# SparkFun_IMU_Breakout_ICM-20948.net
KiCad netlist of a schematic drawn in EAGLE
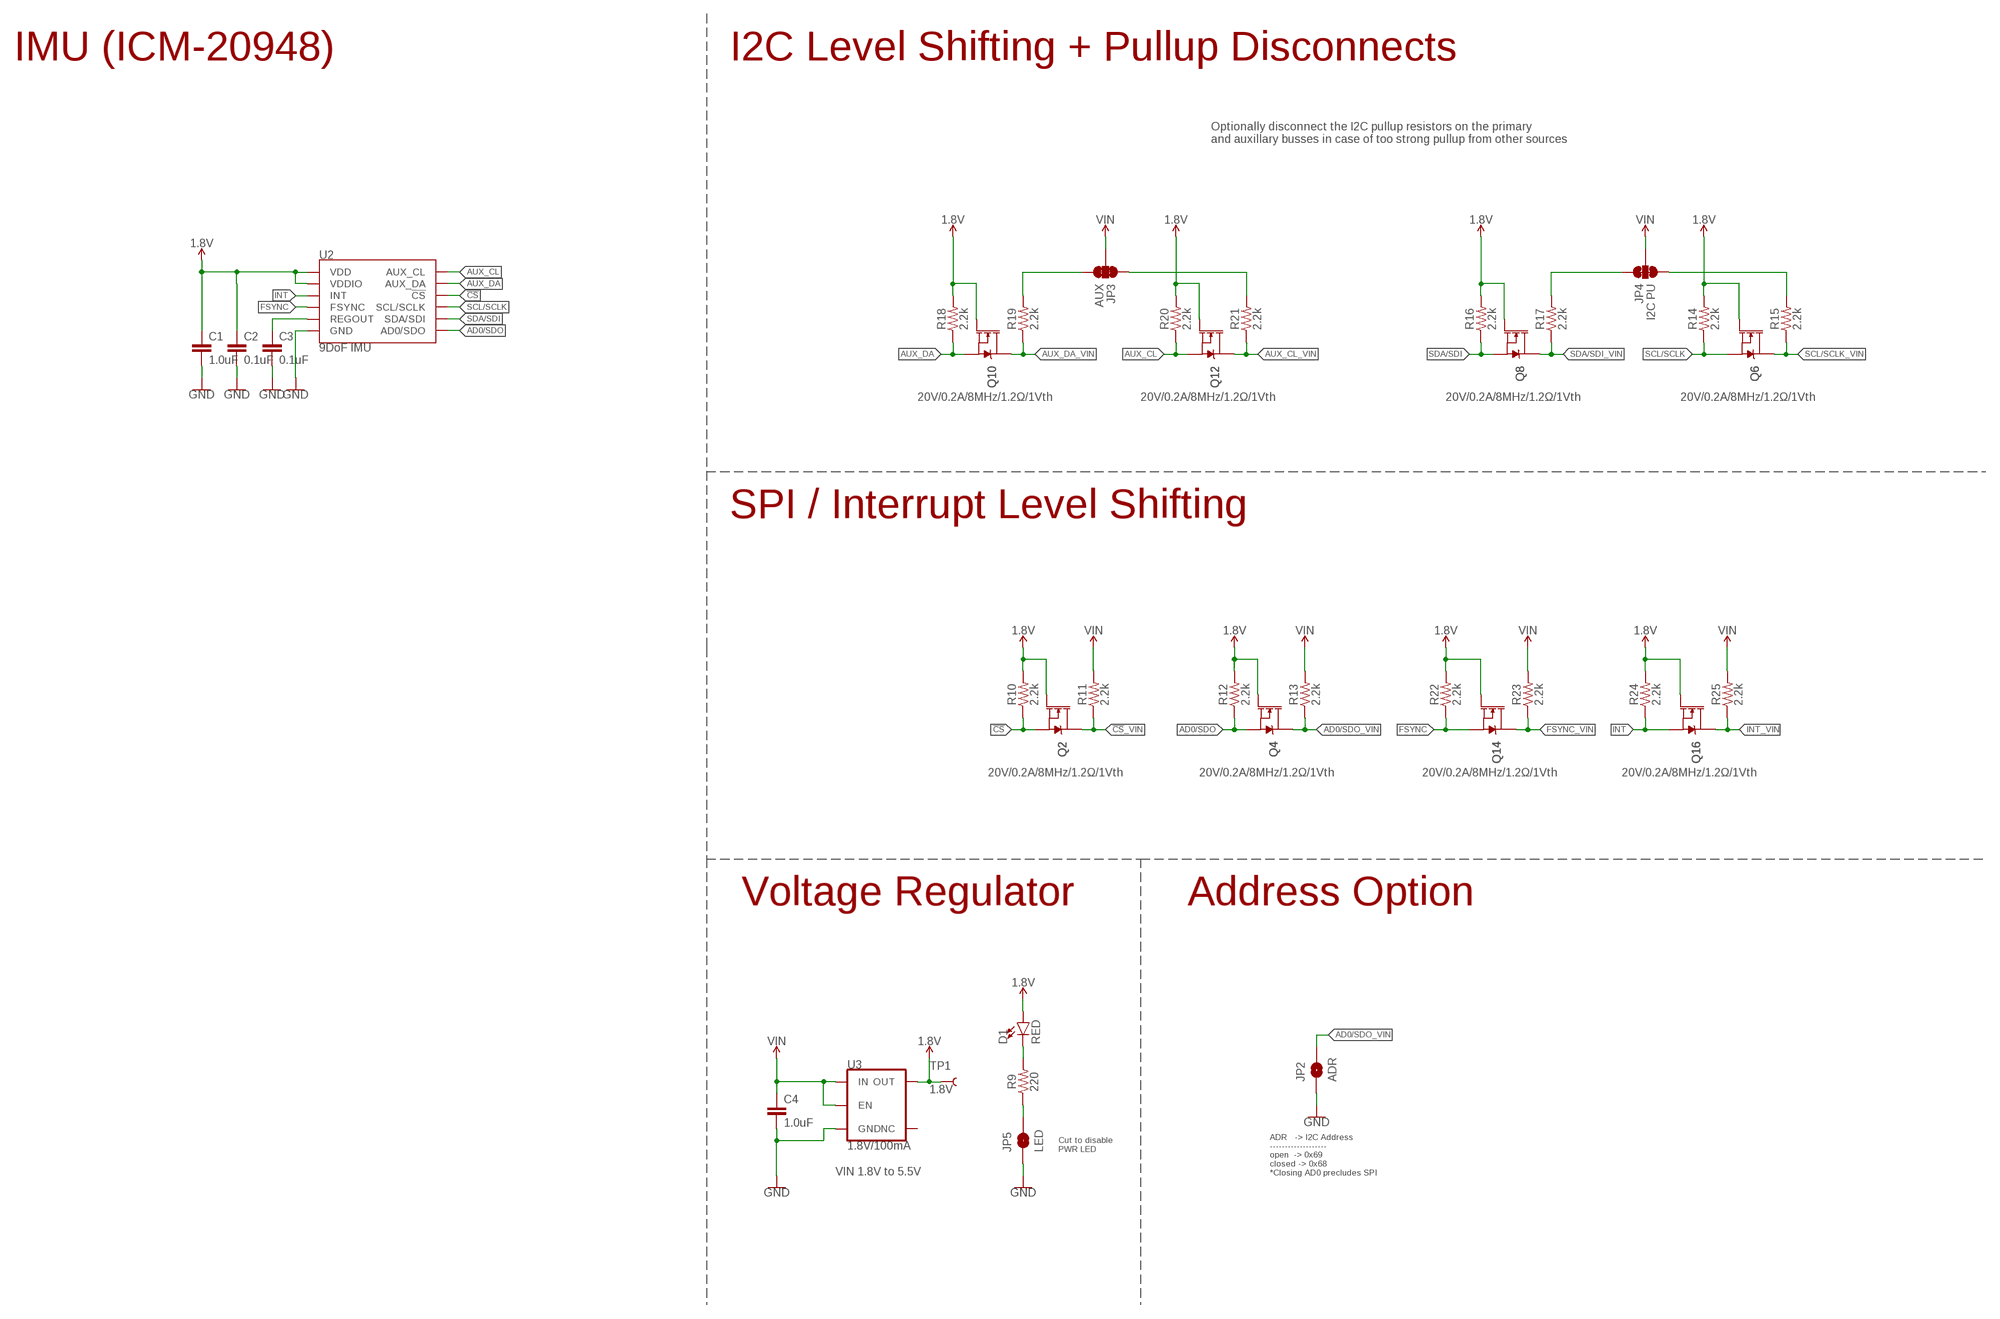
[diagram p0: schematic, sheet 1]

(export (version "E")
  (design (tool "Eeschema 10.0.6"))
  (components
    (comp (ref "C1")
      (value "1.0uF")
      (footprint "eagle-import:0603")
      (libsource (lib "eagle-import") (part "1.0UF-0603-16V-10%-X7R"))
    )
    (comp (ref "C2")
      (value "0.1uF")
      (footprint "eagle-import:0603")
      (libsource (lib "eagle-import") (part "0.1UF-0603-25V-5%"))
    )
    (comp (ref "C3")
      (value "0.1uF")
      (footprint "eagle-import:0603")
      (libsource (lib "eagle-import") (part "0.1UF-0603-25V-5%"))
    )
    (comp (ref "C4")
      (value "1.0uF")
      (footprint "eagle-import:0603")
      (libsource (lib "eagle-import") (part "1.0UF-0603-16V-10%-X7R"))
    )
    (comp (ref "D1")
      (value "RED")
      (footprint "eagle-import:LED-0603")
      (libsource (lib "eagle-import") (part "LED-RED0603"))
    )
    (comp (ref "JP2")
      (value "ADR")
      (footprint "eagle-import:SMT-JUMPER_2_NO_SILK")
      (libsource (lib "eagle-import") (part "JUMPER-SMT_2_NO_SILK"))
    )
    (comp (ref "JP3")
      (value "AUX")
      (footprint "eagle-import:SMT-JUMPER_3_2-NC_TRACE_SILK")
      (libsource (lib "eagle-import") (part "JUMPER-SMT_3_2-NC_TRACE_SILK"))
    )
    (comp (ref "JP4")
      (value "I2C PU")
      (footprint "eagle-import:SMT-JUMPER_3_2-NC_TRACE_SILK")
      (libsource (lib "eagle-import") (part "JUMPER-SMT_3_2-NC_TRACE_SILK"))
    )
    (comp (ref "JP5")
      (value "LED")
      (footprint "eagle-import:SMT-JUMPER_2_NC_TRACE_SILK")
      (libsource (lib "eagle-import") (part "JUMPER-SMT_2_NC_TRACE_SILK"))
    )
    (comp (ref "Q2")
      (value "20V/0.2A/8MHz/1.2Ω/1Vth")
      (footprint "eagle-import:SOT-416FL")
      (libsource (lib "eagle-import") (part "MOSFET-NCH-RE1C002UN"))
    )
    (comp (ref "Q4")
      (value "20V/0.2A/8MHz/1.2Ω/1Vth")
      (footprint "eagle-import:SOT-416FL")
      (libsource (lib "eagle-import") (part "MOSFET-NCH-RE1C002UN"))
    )
    (comp (ref "Q6")
      (value "20V/0.2A/8MHz/1.2Ω/1Vth")
      (footprint "eagle-import:SOT-416FL")
      (libsource (lib "eagle-import") (part "MOSFET-NCH-RE1C002UN"))
    )
    (comp (ref "Q8")
      (value "20V/0.2A/8MHz/1.2Ω/1Vth")
      (footprint "eagle-import:SOT-416FL")
      (libsource (lib "eagle-import") (part "MOSFET-NCH-RE1C002UN"))
    )
    (comp (ref "Q10")
      (value "20V/0.2A/8MHz/1.2Ω/1Vth")
      (footprint "eagle-import:SOT-416FL")
      (libsource (lib "eagle-import") (part "MOSFET-NCH-RE1C002UN"))
    )
    (comp (ref "Q12")
      (value "20V/0.2A/8MHz/1.2Ω/1Vth")
      (footprint "eagle-import:SOT-416FL")
      (libsource (lib "eagle-import") (part "MOSFET-NCH-RE1C002UN"))
    )
    (comp (ref "Q14")
      (value "20V/0.2A/8MHz/1.2Ω/1Vth")
      (footprint "eagle-import:SOT-416FL")
      (libsource (lib "eagle-import") (part "MOSFET-NCH-RE1C002UN"))
    )
    (comp (ref "Q16")
      (value "20V/0.2A/8MHz/1.2Ω/1Vth")
      (footprint "eagle-import:SOT-416FL")
      (libsource (lib "eagle-import") (part "MOSFET-NCH-RE1C002UN"))
    )
    (comp (ref "R9")
      (value "220")
      (footprint "eagle-import:0603")
      (libsource (lib "eagle-import") (part "220OHM-0603-1/10W-1%"))
    )
    (comp (ref "R10")
      (value "2.2k")
      (footprint "eagle-import:0402-TIGHT")
      (libsource (lib "eagle-import") (part "2.2KOHM-0402T-1/16W-1%"))
    )
    (comp (ref "R11")
      (value "2.2k")
      (footprint "eagle-import:0402-TIGHT")
      (libsource (lib "eagle-import") (part "2.2KOHM-0402T-1/16W-1%"))
    )
    (comp (ref "R12")
      (value "2.2k")
      (footprint "eagle-import:0402-TIGHT")
      (libsource (lib "eagle-import") (part "2.2KOHM-0402T-1/16W-1%"))
    )
    (comp (ref "R13")
      (value "2.2k")
      (footprint "eagle-import:0402-TIGHT")
      (libsource (lib "eagle-import") (part "2.2KOHM-0402T-1/16W-1%"))
    )
    (comp (ref "R14")
      (value "2.2k")
      (footprint "eagle-import:0402-TIGHT")
      (libsource (lib "eagle-import") (part "2.2KOHM-0402T-1/16W-1%"))
    )
    (comp (ref "R15")
      (value "2.2k")
      (footprint "eagle-import:0402-TIGHT")
      (libsource (lib "eagle-import") (part "2.2KOHM-0402T-1/16W-1%"))
    )
    (comp (ref "R16")
      (value "2.2k")
      (footprint "eagle-import:0402-TIGHT")
      (libsource (lib "eagle-import") (part "2.2KOHM-0402T-1/16W-1%"))
    )
    (comp (ref "R17")
      (value "2.2k")
      (footprint "eagle-import:0402-TIGHT")
      (libsource (lib "eagle-import") (part "2.2KOHM-0402T-1/16W-1%"))
    )
    (comp (ref "R18")
      (value "2.2k")
      (footprint "eagle-import:0402-TIGHT")
      (libsource (lib "eagle-import") (part "2.2KOHM-0402T-1/16W-1%"))
    )
    (comp (ref "R19")
      (value "2.2k")
      (footprint "eagle-import:0402-TIGHT")
      (libsource (lib "eagle-import") (part "2.2KOHM-0402T-1/16W-1%"))
    )
    (comp (ref "R20")
      (value "2.2k")
      (footprint "eagle-import:0402-TIGHT")
      (libsource (lib "eagle-import") (part "2.2KOHM-0402T-1/16W-1%"))
    )
    (comp (ref "R21")
      (value "2.2k")
      (footprint "eagle-import:0402-TIGHT")
      (libsource (lib "eagle-import") (part "2.2KOHM-0402T-1/16W-1%"))
    )
    (comp (ref "R22")
      (value "2.2k")
      (footprint "eagle-import:0402-TIGHT")
      (libsource (lib "eagle-import") (part "2.2KOHM-0402T-1/16W-1%"))
    )
    (comp (ref "R23")
      (value "2.2k")
      (footprint "eagle-import:0402-TIGHT")
      (libsource (lib "eagle-import") (part "2.2KOHM-0402T-1/16W-1%"))
    )
    (comp (ref "R24")
      (value "2.2k")
      (footprint "eagle-import:0402-TIGHT")
      (libsource (lib "eagle-import") (part "2.2KOHM-0402T-1/16W-1%"))
    )
    (comp (ref "R25")
      (value "2.2k")
      (footprint "eagle-import:0402-TIGHT")
      (libsource (lib "eagle-import") (part "2.2KOHM-0402T-1/16W-1%"))
    )
    (comp (ref "TP1")
      (value "1.8V")
      (footprint "eagle-import:PAD.03X.03")
      (libsource (lib "eagle-import") (part "TEST-POINT3"))
    )
    (comp (ref "U2")
      (value "9DoF IMU")
      (footprint "eagle-import:QFN24-3X3")
      (libsource (lib "eagle-import") (part "ICM-20948"))
    )
    (comp (ref "U3")
      (value "1.8V/100mA")
      (footprint "eagle-import:SC70")
      (libsource (lib "eagle-import") (part "V_REG_SP6214-1.8V"))
    )
  )
  (nets
    (net (code "1") (name "/~{CS}") (class "Default")
      (node (ref "Q2") (pin "2") (pinfunction "S_2") (pintype "bidirectional"))
      (node (ref "R10") (pin "1") (pinfunction "1_1") (pintype "passive"))
      (node (ref "U2") (pin "22") (pinfunction "~{CS}_22") (pintype "bidirectional"))
    )
    (net (code "2") (name "/~{CS}_VIN") (class "Default")
      (node (ref "Q2") (pin "3") (pinfunction "D_3") (pintype "bidirectional"))
      (node (ref "R11") (pin "1") (pinfunction "1_1") (pintype "passive"))
    )
    (net (code "3") (name "1.8V") (class "Default")
      (node (ref "C1") (pin "1") (pinfunction "1_1") (pintype "passive"))
      (node (ref "C2") (pin "1") (pinfunction "1_1") (pintype "passive"))
      (node (ref "D1") (pin "A") (pinfunction "A_A") (pintype "passive"))
      (node (ref "Q10") (pin "1") (pinfunction "G_1") (pintype "bidirectional"))
      (node (ref "Q12") (pin "1") (pinfunction "G_1") (pintype "bidirectional"))
      (node (ref "Q14") (pin "1") (pinfunction "G_1") (pintype "bidirectional"))
      (node (ref "Q16") (pin "1") (pinfunction "G_1") (pintype "bidirectional"))
      (node (ref "Q2") (pin "1") (pinfunction "G_1") (pintype "bidirectional"))
      (node (ref "Q4") (pin "1") (pinfunction "G_1") (pintype "bidirectional"))
      (node (ref "Q6") (pin "1") (pinfunction "G_1") (pintype "bidirectional"))
      (node (ref "Q8") (pin "1") (pinfunction "G_1") (pintype "bidirectional"))
      (node (ref "R10") (pin "2") (pinfunction "2_2") (pintype "passive"))
      (node (ref "R12") (pin "2") (pinfunction "2_2") (pintype "passive"))
      (node (ref "R14") (pin "2") (pinfunction "2_2") (pintype "passive"))
      (node (ref "R16") (pin "2") (pinfunction "2_2") (pintype "passive"))
      (node (ref "R18") (pin "2") (pinfunction "2_2") (pintype "passive"))
      (node (ref "R20") (pin "2") (pinfunction "2_2") (pintype "passive"))
      (node (ref "R22") (pin "2") (pinfunction "2_2") (pintype "passive"))
      (node (ref "R24") (pin "2") (pinfunction "2_2") (pintype "passive"))
      (node (ref "TP1") (pin "P$1") (pinfunction "1_P$1") (pintype "bidirectional"))
      (node (ref "U2") (pin "13") (pinfunction "VDD_13") (pintype "bidirectional"))
      (node (ref "U2") (pin "8") (pinfunction "VDDIO_8") (pintype "bidirectional"))
      (node (ref "U3") (pin "5") (pinfunction "OUT_5") (pintype "passive"))
    )
    (net (code "4") (name "AD0{slash}SDO") (class "Default")
      (node (ref "Q4") (pin "2") (pinfunction "S_2") (pintype "bidirectional"))
      (node (ref "R12") (pin "1") (pinfunction "1_1") (pintype "passive"))
      (node (ref "U2") (pin "9") (pinfunction "AD0/SDO_9") (pintype "bidirectional"))
    )
    (net (code "5") (name "AD0{slash}SDO_VIN") (class "Default")
      (node (ref "JP2") (pin "2") (pinfunction "2_2") (pintype "passive"))
      (node (ref "Q4") (pin "3") (pinfunction "D_3") (pintype "bidirectional"))
      (node (ref "R13") (pin "1") (pinfunction "1_1") (pintype "passive"))
    )
    (net (code "6") (name "AUX_CL") (class "Default")
      (node (ref "Q12") (pin "2") (pinfunction "S_2") (pintype "bidirectional"))
      (node (ref "R20") (pin "1") (pinfunction "1_1") (pintype "passive"))
      (node (ref "U2") (pin "7") (pinfunction "AUX_CL_7") (pintype "bidirectional"))
    )
    (net (code "7") (name "AUX_CL_VIN") (class "Default")
      (node (ref "Q12") (pin "3") (pinfunction "D_3") (pintype "bidirectional"))
      (node (ref "R21") (pin "1") (pinfunction "1_1") (pintype "passive"))
    )
    (net (code "8") (name "AUX_DA") (class "Default")
      (node (ref "Q10") (pin "2") (pinfunction "S_2") (pintype "bidirectional"))
      (node (ref "R18") (pin "1") (pinfunction "1_1") (pintype "passive"))
      (node (ref "U2") (pin "21") (pinfunction "AUX_DA_21") (pintype "bidirectional"))
    )
    (net (code "9") (name "AUX_DA_VIN") (class "Default")
      (node (ref "Q10") (pin "3") (pinfunction "D_3") (pintype "bidirectional"))
      (node (ref "R19") (pin "1") (pinfunction "1_1") (pintype "passive"))
    )
    (net (code "10") (name "FSYNC") (class "Default")
      (node (ref "Q14") (pin "2") (pinfunction "S_2") (pintype "bidirectional"))
      (node (ref "R22") (pin "1") (pinfunction "1_1") (pintype "passive"))
      (node (ref "U2") (pin "11") (pinfunction "FSYNC_11") (pintype "bidirectional"))
    )
    (net (code "11") (name "FSYNC_VIN") (class "Default")
      (node (ref "Q14") (pin "3") (pinfunction "D_3") (pintype "bidirectional"))
      (node (ref "R23") (pin "1") (pinfunction "1_1") (pintype "passive"))
    )
    (net (code "12") (name "GND") (class "Default")
      (node (ref "C1") (pin "2") (pinfunction "2_2") (pintype "passive"))
      (node (ref "C2") (pin "2") (pinfunction "2_2") (pintype "passive"))
      (node (ref "C3") (pin "2") (pinfunction "2_2") (pintype "passive"))
      (node (ref "C4") (pin "2") (pinfunction "2_2") (pintype "passive"))
      (node (ref "JP2") (pin "1") (pinfunction "1_1") (pintype "passive"))
      (node (ref "JP5") (pin "1") (pinfunction "1_1") (pintype "passive"))
      (node (ref "U2") (pin "18") (pinfunction "GND_18") (pintype "bidirectional"))
      (node (ref "U2") (pin "20") (pinfunction "GND_20") (pintype "bidirectional"))
      (node (ref "U3") (pin "2") (pinfunction "GND_2") (pintype "input"))
    )
    (net (code "13") (name "INT") (class "Default")
      (node (ref "Q16") (pin "2") (pinfunction "S_2") (pintype "bidirectional"))
      (node (ref "R24") (pin "1") (pinfunction "1_1") (pintype "passive"))
      (node (ref "U2") (pin "12") (pinfunction "INT_12") (pintype "bidirectional"))
    )
    (net (code "14") (name "INT_VIN") (class "Default")
      (node (ref "Q16") (pin "3") (pinfunction "D_3") (pintype "bidirectional"))
      (node (ref "R25") (pin "1") (pinfunction "1_1") (pintype "passive"))
    )
    (net (code "15") (name "Net-(D1-PadC)") (class "Default")
      (node (ref "D1") (pin "C") (pinfunction "C_C") (pintype "passive"))
      (node (ref "R9") (pin "2") (pinfunction "2_2") (pintype "passive"))
    )
    (net (code "16") (name "Net-(JP3-Pad1)") (class "Default")
      (node (ref "JP3") (pin "1") (pinfunction "1_1") (pintype "passive"))
      (node (ref "R21") (pin "2") (pinfunction "2_2") (pintype "passive"))
    )
    (net (code "17") (name "Net-(JP3-Pad3)") (class "Default")
      (node (ref "JP3") (pin "3") (pinfunction "3_3") (pintype "passive"))
      (node (ref "R19") (pin "2") (pinfunction "2_2") (pintype "passive"))
    )
    (net (code "18") (name "Net-(JP4-Pad1)") (class "Default")
      (node (ref "JP4") (pin "1") (pinfunction "1_1") (pintype "passive"))
      (node (ref "R17") (pin "2") (pinfunction "2_2") (pintype "passive"))
    )
    (net (code "19") (name "Net-(JP4-Pad3)") (class "Default")
      (node (ref "JP4") (pin "3") (pinfunction "3_3") (pintype "passive"))
      (node (ref "R15") (pin "2") (pinfunction "2_2") (pintype "passive"))
    )
    (net (code "20") (name "Net-(JP5-Pad2)") (class "Default")
      (node (ref "JP5") (pin "2") (pinfunction "2_2") (pintype "passive"))
      (node (ref "R9") (pin "1") (pinfunction "1_1") (pintype "passive"))
    )
    (net (code "21") (name "Net-(U2-REGOUT)") (class "Default")
      (node (ref "C3") (pin "1") (pinfunction "1_1") (pintype "passive"))
      (node (ref "U2") (pin "10") (pinfunction "REGOUT_10") (pintype "bidirectional"))
    )
    (net (code "22") (name "SCL{slash}SCLK") (class "Default")
      (node (ref "Q6") (pin "2") (pinfunction "S_2") (pintype "bidirectional"))
      (node (ref "R14") (pin "1") (pinfunction "1_1") (pintype "passive"))
      (node (ref "U2") (pin "23") (pinfunction "SCL/SCLK_23") (pintype "bidirectional"))
    )
    (net (code "23") (name "SCL{slash}SCLK_VIN") (class "Default")
      (node (ref "Q6") (pin "3") (pinfunction "D_3") (pintype "bidirectional"))
      (node (ref "R15") (pin "1") (pinfunction "1_1") (pintype "passive"))
    )
    (net (code "24") (name "SDA{slash}SDI") (class "Default")
      (node (ref "Q8") (pin "2") (pinfunction "S_2") (pintype "bidirectional"))
      (node (ref "R16") (pin "1") (pinfunction "1_1") (pintype "passive"))
      (node (ref "U2") (pin "24") (pinfunction "SDA/SDI_24") (pintype "bidirectional"))
    )
    (net (code "25") (name "SDA{slash}SDI_VIN") (class "Default")
      (node (ref "Q8") (pin "3") (pinfunction "D_3") (pintype "bidirectional"))
      (node (ref "R17") (pin "1") (pinfunction "1_1") (pintype "passive"))
    )
    (net (code "26") (name "VIN") (class "Default")
      (node (ref "C4") (pin "1") (pinfunction "1_1") (pintype "passive"))
      (node (ref "JP3") (pin "2") (pinfunction "2_2") (pintype "passive"))
      (node (ref "JP4") (pin "2") (pinfunction "2_2") (pintype "passive"))
      (node (ref "R11") (pin "2") (pinfunction "2_2") (pintype "passive"))
      (node (ref "R13") (pin "2") (pinfunction "2_2") (pintype "passive"))
      (node (ref "R23") (pin "2") (pinfunction "2_2") (pintype "passive"))
      (node (ref "R25") (pin "2") (pinfunction "2_2") (pintype "passive"))
      (node (ref "U3") (pin "1") (pinfunction "IN_1") (pintype "input"))
      (node (ref "U3") (pin "3") (pinfunction "EN_3") (pintype "input"))
    )
    (net (code "27") (name "unconnected-(U3-NC-Pad4)") (class "Default")
      (node (ref "U3") (pin "4") (pinfunction "NC_4") (pintype "no_connect"))
    )
  )
)
